# R401H.net
KiCad netlist of a schematic drawn in EAGLE
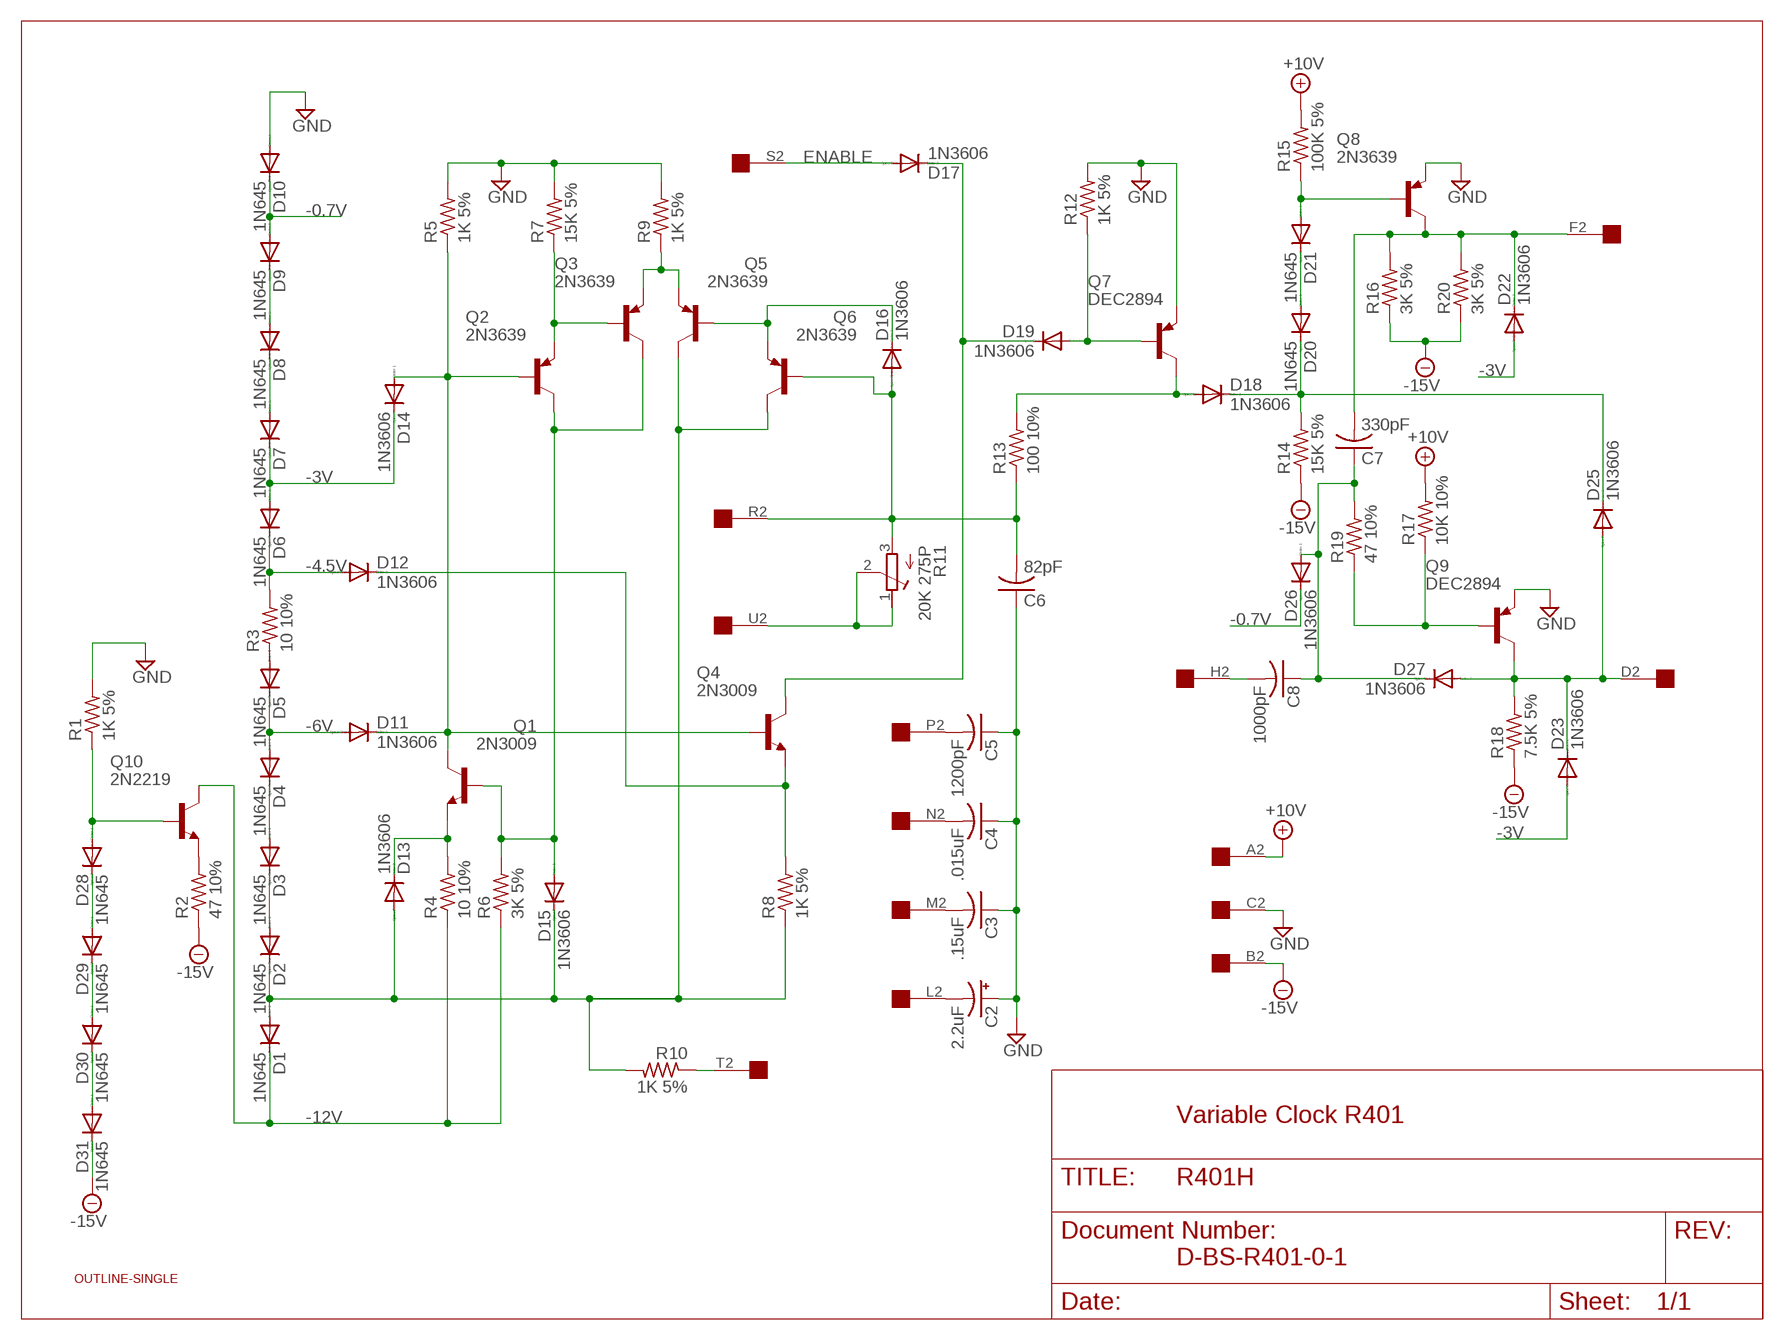
[diagram p0: schematic, sheet 1]

(export (version "E")
  (design (tool "Eeschema 10.0.6"))
  (components
    (comp (ref "C2")
      (value "2.2uF")
      (footprint "eagle-import:E12-4")
      (libsource (lib "eagle-import") (part "CPOL-USE12-4AXIAL"))
    )
    (comp (ref "C3")
      (value ".15uF")
      (footprint "eagle-import:C225-062X268")
      (libsource (lib "eagle-import") (part "C-US225-062X268"))
    )
    (comp (ref "C4")
      (value ".015uF")
      (footprint "eagle-import:C102-043X133")
      (libsource (lib "eagle-import") (part "C-US102-043X133"))
    )
    (comp (ref "C5")
      (value "1200pF")
      (footprint "eagle-import:C150-054X183")
      (libsource (lib "eagle-import") (part "C-US150-054X183"))
    )
    (comp (ref "C6")
      (value "82pF")
      (footprint "eagle-import:C102-043X133")
      (libsource (lib "eagle-import") (part "C-US102-043X133"))
    )
    (comp (ref "C7")
      (value "330pF")
      (footprint "eagle-import:C150-054X183")
      (libsource (lib "eagle-import") (part "C-US150-054X183"))
    )
    (comp (ref "C8")
      (value "1000pF")
      (footprint "eagle-import:C150-054X183")
      (libsource (lib "eagle-import") (part "C-US150-054X183"))
    )
    (comp (ref "D1")
      (value "1N645")
      (footprint "eagle-import:DO35-10")
      (libsource (lib "eagle-import") (part "1N4148DO35-10"))
    )
    (comp (ref "D2")
      (value "1N645")
      (footprint "eagle-import:DO35-10")
      (libsource (lib "eagle-import") (part "1N4148DO35-10"))
    )
    (comp (ref "D3")
      (value "1N645")
      (footprint "eagle-import:DO35-10")
      (libsource (lib "eagle-import") (part "1N4148DO35-10"))
    )
    (comp (ref "D4")
      (value "1N645")
      (footprint "eagle-import:DO35-10")
      (libsource (lib "eagle-import") (part "1N4148DO35-10"))
    )
    (comp (ref "D5")
      (value "1N645")
      (footprint "eagle-import:DO35-10")
      (libsource (lib "eagle-import") (part "1N4148DO35-10"))
    )
    (comp (ref "D6")
      (value "1N645")
      (footprint "eagle-import:DO35-10")
      (libsource (lib "eagle-import") (part "1N4148DO35-10"))
    )
    (comp (ref "D7")
      (value "1N645")
      (footprint "eagle-import:DO35-10")
      (libsource (lib "eagle-import") (part "1N4148DO35-10"))
    )
    (comp (ref "D8")
      (value "1N645")
      (footprint "eagle-import:DO35-10")
      (libsource (lib "eagle-import") (part "1N4148DO35-10"))
    )
    (comp (ref "D9")
      (value "1N645")
      (footprint "eagle-import:DO35-10")
      (libsource (lib "eagle-import") (part "1N4148DO35-10"))
    )
    (comp (ref "D10")
      (value "1N645")
      (footprint "eagle-import:DO35-10")
      (libsource (lib "eagle-import") (part "1N4148DO35-10"))
    )
    (comp (ref "D11")
      (value "1N3606")
      (footprint "eagle-import:DO35-10")
      (libsource (lib "eagle-import") (part "1N4148DO35-10"))
    )
    (comp (ref "D12")
      (value "1N3606")
      (footprint "eagle-import:DO35-10")
      (libsource (lib "eagle-import") (part "1N4148DO35-10"))
    )
    (comp (ref "D13")
      (value "1N3606")
      (footprint "eagle-import:DO35-10")
      (libsource (lib "eagle-import") (part "1N4148DO35-10"))
    )
    (comp (ref "D14")
      (value "1N3606")
      (footprint "eagle-import:DO35-10")
      (libsource (lib "eagle-import") (part "1N4148DO35-10"))
    )
    (comp (ref "D15")
      (value "1N3606")
      (footprint "eagle-import:DO35-10")
      (libsource (lib "eagle-import") (part "1N4148DO35-10"))
    )
    (comp (ref "D16")
      (value "1N3606")
      (footprint "eagle-import:DO35-10")
      (libsource (lib "eagle-import") (part "1N4148DO35-10"))
    )
    (comp (ref "D17")
      (value "1N3606")
      (footprint "eagle-import:DO35-10")
      (libsource (lib "eagle-import") (part "1N4148DO35-10"))
    )
    (comp (ref "D18")
      (value "1N3606")
      (footprint "eagle-import:DO35-10")
      (libsource (lib "eagle-import") (part "1N4148DO35-10"))
    )
    (comp (ref "D19")
      (value "1N3606")
      (footprint "eagle-import:DO35-10")
      (libsource (lib "eagle-import") (part "1N4148DO35-10"))
    )
    (comp (ref "D20")
      (value "1N645")
      (footprint "eagle-import:DO35-10")
      (libsource (lib "eagle-import") (part "1N4148DO35-10"))
    )
    (comp (ref "D21")
      (value "1N645")
      (footprint "eagle-import:DO35-10")
      (libsource (lib "eagle-import") (part "1N4148DO35-10"))
    )
    (comp (ref "D22")
      (value "1N3606")
      (footprint "eagle-import:DO35-10")
      (libsource (lib "eagle-import") (part "1N4148DO35-10"))
    )
    (comp (ref "D23")
      (value "1N3606")
      (footprint "eagle-import:DO35-10")
      (libsource (lib "eagle-import") (part "1N4148DO35-10"))
    )
    (comp (ref "D25")
      (value "1N3606")
      (footprint "eagle-import:DO35-10")
      (libsource (lib "eagle-import") (part "1N4148DO35-10"))
    )
    (comp (ref "D26")
      (value "1N3606")
      (footprint "eagle-import:DO35-10")
      (libsource (lib "eagle-import") (part "1N4148DO35-10"))
    )
    (comp (ref "D27")
      (value "1N3606")
      (footprint "eagle-import:DO35-10")
      (libsource (lib "eagle-import") (part "1N4148DO35-10"))
    )
    (comp (ref "D28")
      (value "1N645")
      (footprint "eagle-import:DO35-10")
      (libsource (lib "eagle-import") (part "1N4148DO35-10"))
    )
    (comp (ref "D29")
      (value "1N645")
      (footprint "eagle-import:DO35-10")
      (libsource (lib "eagle-import") (part "1N4148DO35-10"))
    )
    (comp (ref "D30")
      (value "1N645")
      (footprint "eagle-import:DO35-10")
      (libsource (lib "eagle-import") (part "1N4148DO35-10"))
    )
    (comp (ref "D31")
      (value "1N645")
      (footprint "eagle-import:DO35-10")
      (libsource (lib "eagle-import") (part "1N4148DO35-10"))
    )
    (comp (ref "Q1")
      (value "2N3009")
      (footprint "eagle-import:TO5")
      (libsource (lib "eagle-import") (part "2N2102"))
    )
    (comp (ref "Q2")
      (value "2N3639")
      (footprint "eagle-import:TO39")
      (libsource (lib "eagle-import") (part "2N2904"))
    )
    (comp (ref "Q3")
      (value "2N3639")
      (footprint "eagle-import:TO39")
      (libsource (lib "eagle-import") (part "2N2904"))
    )
    (comp (ref "Q4")
      (value "2N3009")
      (footprint "eagle-import:TO5")
      (libsource (lib "eagle-import") (part "2N2102"))
    )
    (comp (ref "Q5")
      (value "2N3639")
      (footprint "eagle-import:TO39")
      (libsource (lib "eagle-import") (part "2N2904"))
    )
    (comp (ref "Q6")
      (value "2N3639")
      (footprint "eagle-import:TO39")
      (libsource (lib "eagle-import") (part "2N2904"))
    )
    (comp (ref "Q7")
      (value "DEC2894")
      (footprint "eagle-import:TO39")
      (libsource (lib "eagle-import") (part "2N2904"))
    )
    (comp (ref "Q8")
      (value "2N3639")
      (footprint "eagle-import:TO39")
      (libsource (lib "eagle-import") (part "2N2904"))
    )
    (comp (ref "Q9")
      (value "DEC2894")
      (footprint "eagle-import:TO39")
      (libsource (lib "eagle-import") (part "2N2904"))
    )
    (comp (ref "Q10")
      (value "2N2219")
      (footprint "eagle-import:TO5")
      (libsource (lib "eagle-import") (part "2N2102"))
    )
    (comp (ref "R1")
      (value "1K 5%")
      (footprint "eagle-import:0207_10")
      (libsource (lib "eagle-import") (part "R-US_0207/10"))
    )
    (comp (ref "R2")
      (value "47 10%")
      (footprint "eagle-import:0207_10")
      (libsource (lib "eagle-import") (part "R-US_0207/10"))
    )
    (comp (ref "R3")
      (value "10 10%")
      (footprint "eagle-import:0207_10")
      (libsource (lib "eagle-import") (part "R-US_0207/10"))
    )
    (comp (ref "R4")
      (value "10 10%")
      (footprint "eagle-import:0207_10")
      (libsource (lib "eagle-import") (part "R-US_0207/10"))
    )
    (comp (ref "R5")
      (value "1K 5%")
      (footprint "eagle-import:0207_10")
      (libsource (lib "eagle-import") (part "R-US_0207/10"))
    )
    (comp (ref "R6")
      (value "3K 5%")
      (footprint "eagle-import:0207_10")
      (libsource (lib "eagle-import") (part "R-US_0207/10"))
    )
    (comp (ref "R7")
      (value "15K 5%")
      (footprint "eagle-import:0207_10")
      (libsource (lib "eagle-import") (part "R-US_0207/10"))
    )
    (comp (ref "R8")
      (value "1K 5%")
      (footprint "eagle-import:0207_10")
      (libsource (lib "eagle-import") (part "R-US_0207/10"))
    )
    (comp (ref "R9")
      (value "1K 5%")
      (footprint "eagle-import:0207_10")
      (libsource (lib "eagle-import") (part "R-US_0207/10"))
    )
    (comp (ref "R10")
      (value "1K 5%")
      (footprint "eagle-import:0207_10")
      (libsource (lib "eagle-import") (part "R-US_0207/10"))
    )
    (comp (ref "R11")
      (value "20K 275P")
      (footprint "eagle-import:3006Y")
      (libsource (lib "eagle-import") (part "275P"))
    )
    (comp (ref "R12")
      (value "1K 5%")
      (footprint "eagle-import:0207_10")
      (libsource (lib "eagle-import") (part "R-US_0207/10"))
    )
    (comp (ref "R13")
      (value "100 10%")
      (footprint "eagle-import:0207_10")
      (libsource (lib "eagle-import") (part "R-US_0207/10"))
    )
    (comp (ref "R14")
      (value "15K 5%")
      (footprint "eagle-import:0207_10")
      (libsource (lib "eagle-import") (part "R-US_0207/10"))
    )
    (comp (ref "R15")
      (value "100K 5%")
      (footprint "eagle-import:0207_10")
      (libsource (lib "eagle-import") (part "R-US_0207/10"))
    )
    (comp (ref "R16")
      (value "3K 5%")
      (footprint "eagle-import:0207_10")
      (libsource (lib "eagle-import") (part "R-US_0207/10"))
    )
    (comp (ref "R17")
      (value "10K 10%")
      (footprint "eagle-import:0207_10")
      (libsource (lib "eagle-import") (part "R-US_0207/10"))
    )
    (comp (ref "R18")
      (value "7.5K 5%")
      (footprint "eagle-import:0207_10")
      (libsource (lib "eagle-import") (part "R-US_0207/10"))
    )
    (comp (ref "R19")
      (value "47 10%")
      (footprint "eagle-import:0207_10")
      (libsource (lib "eagle-import") (part "R-US_0207/10"))
    )
    (comp (ref "R20")
      (value "3K 5%")
      (footprint "eagle-import:0207_10")
      (libsource (lib "eagle-import") (part "R-US_0207/10"))
    )
    (comp (ref "U$1")
      (value "OUTLINE-SINGLE")
      (footprint "eagle-import:SINGLE")
      (libsource (lib "eagle-import") (part "OUTLINE-SINGLE"))
    )
    (comp (ref "U$2")
      (value "EDGE-1")
      (footprint "eagle-import:EDGE-CON1")
      (libsource (lib "eagle-import") (part "EDGE-1"))
    )
  )
  (nets
    (net (code "1") (name "+10V") (class "Default")
      (node (ref "R15") (pin "2") (pinfunction "2_2") (pintype "passive"))
      (node (ref "R17") (pin "2") (pinfunction "2_2") (pintype "passive"))
      (node (ref "U$2") (pin "A2") (pinfunction "1_A2") (pintype "bidirectional"))
    )
    (net (code "2") (name "-15V") (class "Default")
      (node (ref "D31") (pin "C") (pinfunction "C_C") (pintype "passive"))
      (node (ref "R14") (pin "1") (pinfunction "1_1") (pintype "passive"))
      (node (ref "R16") (pin "1") (pinfunction "1_1") (pintype "passive"))
      (node (ref "R18") (pin "1") (pinfunction "1_1") (pintype "passive"))
      (node (ref "R2") (pin "1") (pinfunction "1_1") (pintype "passive"))
      (node (ref "R20") (pin "1") (pinfunction "1_1") (pintype "passive"))
      (node (ref "U$2") (pin "B2") (pinfunction "1_B2") (pintype "bidirectional"))
    )
    (net (code "3") (name "/-0.7V") (class "Default")
      (node (ref "D10") (pin "C") (pinfunction "C_C") (pintype "passive"))
      (node (ref "D26") (pin "C") (pinfunction "C_C") (pintype "passive"))
      (node (ref "D9") (pin "A") (pinfunction "A_A") (pintype "passive"))
    )
    (net (code "4") (name "/-3V") (class "Default")
      (node (ref "D14") (pin "C") (pinfunction "C_C") (pintype "passive"))
      (node (ref "D22") (pin "A") (pinfunction "A_A") (pintype "passive"))
      (node (ref "D23") (pin "A") (pinfunction "A_A") (pintype "passive"))
      (node (ref "D6") (pin "A") (pinfunction "A_A") (pintype "passive"))
      (node (ref "D7") (pin "C") (pinfunction "C_C") (pintype "passive"))
    )
    (net (code "5") (name "/-4.5V") (class "Default")
      (node (ref "D12") (pin "A") (pinfunction "A_A") (pintype "passive"))
      (node (ref "D6") (pin "C") (pinfunction "C_C") (pintype "passive"))
      (node (ref "R3") (pin "2") (pinfunction "2_2") (pintype "passive"))
    )
    (net (code "6") (name "/-6V") (class "Default")
      (node (ref "D11") (pin "A") (pinfunction "A_A") (pintype "passive"))
      (node (ref "D4") (pin "A") (pinfunction "A_A") (pintype "passive"))
      (node (ref "D5") (pin "C") (pinfunction "C_C") (pintype "passive"))
    )
    (net (code "7") (name "/-12V") (class "Default")
      (node (ref "D1") (pin "C") (pinfunction "C_C") (pintype "passive"))
      (node (ref "Q10") (pin "3") (pinfunction "C_3") (pintype "passive"))
      (node (ref "R4") (pin "1") (pinfunction "1_1") (pintype "passive"))
      (node (ref "R6") (pin "1") (pinfunction "1_1") (pintype "passive"))
    )
    (net (code "8") (name "/ENABLE") (class "Default")
      (node (ref "D17") (pin "A") (pinfunction "A_A") (pintype "passive"))
      (node (ref "U$2") (pin "S2") (pinfunction "1_S2") (pintype "bidirectional"))
    )
    (net (code "9") (name "GND") (class "Default")
      (node (ref "C2") (pin "+") (pinfunction "+_+") (pintype "passive"))
      (node (ref "C3") (pin "1") (pinfunction "1_1") (pintype "passive"))
      (node (ref "C4") (pin "1") (pinfunction "1_1") (pintype "passive"))
      (node (ref "C5") (pin "1") (pinfunction "1_1") (pintype "passive"))
      (node (ref "C6") (pin "1") (pinfunction "1_1") (pintype "passive"))
      (node (ref "D10") (pin "A") (pinfunction "A_A") (pintype "passive"))
      (node (ref "Q7") (pin "1") (pinfunction "E_1") (pintype "passive"))
      (node (ref "Q8") (pin "1") (pinfunction "E_1") (pintype "passive"))
      (node (ref "Q9") (pin "1") (pinfunction "E_1") (pintype "passive"))
      (node (ref "R1") (pin "2") (pinfunction "2_2") (pintype "passive"))
      (node (ref "R12") (pin "2") (pinfunction "2_2") (pintype "passive"))
      (node (ref "R5") (pin "2") (pinfunction "2_2") (pintype "passive"))
      (node (ref "R7") (pin "2") (pinfunction "2_2") (pintype "passive"))
      (node (ref "R9") (pin "2") (pinfunction "2_2") (pintype "passive"))
      (node (ref "U$2") (pin "C2") (pinfunction "1_C2") (pintype "bidirectional"))
    )
    (net (code "10") (name "Net-(C7-Pad1)") (class "Default")
      (node (ref "C7") (pin "1") (pinfunction "1_1") (pintype "passive"))
      (node (ref "C8") (pin "1") (pinfunction "1_1") (pintype "passive"))
      (node (ref "D26") (pin "A") (pinfunction "A_A") (pintype "passive"))
      (node (ref "D27") (pin "C") (pinfunction "C_C") (pintype "passive"))
      (node (ref "R19") (pin "2") (pinfunction "2_2") (pintype "passive"))
    )
    (net (code "11") (name "Net-(D2-PadA)") (class "Default")
      (node (ref "D2") (pin "A") (pinfunction "A_A") (pintype "passive"))
      (node (ref "D3") (pin "C") (pinfunction "C_C") (pintype "passive"))
    )
    (net (code "12") (name "Net-(D3-PadA)") (class "Default")
      (node (ref "D3") (pin "A") (pinfunction "A_A") (pintype "passive"))
      (node (ref "D4") (pin "C") (pinfunction "C_C") (pintype "passive"))
    )
    (net (code "13") (name "Net-(D5-PadA)") (class "Default")
      (node (ref "D5") (pin "A") (pinfunction "A_A") (pintype "passive"))
      (node (ref "R3") (pin "1") (pinfunction "1_1") (pintype "passive"))
    )
    (net (code "14") (name "Net-(D7-PadA)") (class "Default")
      (node (ref "D7") (pin "A") (pinfunction "A_A") (pintype "passive"))
      (node (ref "D8") (pin "C") (pinfunction "C_C") (pintype "passive"))
    )
    (net (code "15") (name "Net-(D8-PadA)") (class "Default")
      (node (ref "D8") (pin "A") (pinfunction "A_A") (pintype "passive"))
      (node (ref "D9") (pin "C") (pinfunction "C_C") (pintype "passive"))
    )
    (net (code "16") (name "Net-(D18-PadC)") (class "Default")
      (node (ref "D18") (pin "C") (pinfunction "C_C") (pintype "passive"))
      (node (ref "D20") (pin "C") (pinfunction "C_C") (pintype "passive"))
      (node (ref "D25") (pin "C") (pinfunction "C_C") (pintype "passive"))
      (node (ref "R14") (pin "2") (pinfunction "2_2") (pintype "passive"))
    )
    (net (code "17") (name "Net-(D20-PadA)") (class "Default")
      (node (ref "D20") (pin "A") (pinfunction "A_A") (pintype "passive"))
      (node (ref "D21") (pin "C") (pinfunction "C_C") (pintype "passive"))
    )
    (net (code "18") (name "Net-(D28-PadC)") (class "Default")
      (node (ref "D28") (pin "C") (pinfunction "C_C") (pintype "passive"))
      (node (ref "D29") (pin "A") (pinfunction "A_A") (pintype "passive"))
    )
    (net (code "19") (name "Net-(D29-PadC)") (class "Default")
      (node (ref "D29") (pin "C") (pinfunction "C_C") (pintype "passive"))
      (node (ref "D30") (pin "A") (pinfunction "A_A") (pintype "passive"))
    )
    (net (code "20") (name "Net-(D30-PadC)") (class "Default")
      (node (ref "D30") (pin "C") (pinfunction "C_C") (pintype "passive"))
      (node (ref "D31") (pin "A") (pinfunction "A_A") (pintype "passive"))
    )
    (net (code "21") (name "Net-(Q1-B)") (class "Default")
      (node (ref "D15") (pin "A") (pinfunction "A_A") (pintype "passive"))
      (node (ref "Q1") (pin "2") (pinfunction "B_2") (pintype "passive"))
      (node (ref "Q2") (pin "3") (pinfunction "C_3") (pintype "passive"))
      (node (ref "Q3") (pin "3") (pinfunction "C_3") (pintype "passive"))
      (node (ref "R6") (pin "2") (pinfunction "2_2") (pintype "passive"))
    )
    (net (code "22") (name "Net-(Q1-C)") (class "Default")
      (node (ref "D11") (pin "C") (pinfunction "C_C") (pintype "passive"))
      (node (ref "D14") (pin "A") (pinfunction "A_A") (pintype "passive"))
      (node (ref "Q1") (pin "3") (pinfunction "C_3") (pintype "passive"))
      (node (ref "Q2") (pin "2") (pinfunction "B_2") (pintype "passive"))
      (node (ref "Q4") (pin "2") (pinfunction "B_2") (pintype "passive"))
      (node (ref "R5") (pin "1") (pinfunction "1_1") (pintype "passive"))
    )
    (net (code "23") (name "Net-(Q1-E)") (class "Default")
      (node (ref "D13") (pin "C") (pinfunction "C_C") (pintype "passive"))
      (node (ref "Q1") (pin "1") (pinfunction "E_1") (pintype "passive"))
      (node (ref "R4") (pin "2") (pinfunction "2_2") (pintype "passive"))
    )
    (net (code "24") (name "Net-(Q2-E)") (class "Default")
      (node (ref "Q2") (pin "1") (pinfunction "E_1") (pintype "passive"))
      (node (ref "Q3") (pin "2") (pinfunction "B_2") (pintype "passive"))
      (node (ref "R7") (pin "1") (pinfunction "1_1") (pintype "passive"))
    )
    (net (code "25") (name "Net-(Q3-E)") (class "Default")
      (node (ref "Q3") (pin "1") (pinfunction "E_1") (pintype "passive"))
      (node (ref "Q5") (pin "1") (pinfunction "E_1") (pintype "passive"))
      (node (ref "R9") (pin "1") (pinfunction "1_1") (pintype "passive"))
    )
    (net (code "26") (name "Net-(Q4-C)") (class "Default")
      (node (ref "D17") (pin "C") (pinfunction "C_C") (pintype "passive"))
      (node (ref "D19") (pin "C") (pinfunction "C_C") (pintype "passive"))
      (node (ref "Q4") (pin "3") (pinfunction "C_3") (pintype "passive"))
    )
    (net (code "27") (name "Net-(Q4-E)") (class "Default")
      (node (ref "D12") (pin "C") (pinfunction "C_C") (pintype "passive"))
      (node (ref "Q4") (pin "1") (pinfunction "E_1") (pintype "passive"))
      (node (ref "R8") (pin "2") (pinfunction "2_2") (pintype "passive"))
    )
    (net (code "28") (name "Net-(Q5-B)") (class "Default")
      (node (ref "D16") (pin "C") (pinfunction "C_C") (pintype "passive"))
      (node (ref "Q5") (pin "2") (pinfunction "B_2") (pintype "passive"))
      (node (ref "Q6") (pin "1") (pinfunction "E_1") (pintype "passive"))
    )
    (net (code "29") (name "Net-(Q5-C)") (class "Default")
      (node (ref "D1") (pin "A") (pinfunction "A_A") (pintype "passive"))
      (node (ref "D13") (pin "A") (pinfunction "A_A") (pintype "passive"))
      (node (ref "D15") (pin "C") (pinfunction "C_C") (pintype "passive"))
      (node (ref "D2") (pin "C") (pinfunction "C_C") (pintype "passive"))
      (node (ref "Q5") (pin "3") (pinfunction "C_3") (pintype "passive"))
      (node (ref "Q6") (pin "3") (pinfunction "C_3") (pintype "passive"))
      (node (ref "R10") (pin "2") (pinfunction "2_2") (pintype "passive"))
      (node (ref "R8") (pin "1") (pinfunction "1_1") (pintype "passive"))
    )
    (net (code "30") (name "Net-(Q6-B)") (class "Default")
      (node (ref "C6") (pin "2") (pinfunction "2_2") (pintype "passive"))
      (node (ref "D16") (pin "A") (pinfunction "A_A") (pintype "passive"))
      (node (ref "Q6") (pin "2") (pinfunction "B_2") (pintype "passive"))
      (node (ref "R11") (pin "3") (pinfunction "E_3") (pintype "passive"))
      (node (ref "R13") (pin "1") (pinfunction "1_1") (pintype "passive"))
      (node (ref "U$2") (pin "R2") (pinfunction "1_R2") (pintype "bidirectional"))
    )
    (net (code "31") (name "Net-(Q7-B)") (class "Default")
      (node (ref "D19") (pin "A") (pinfunction "A_A") (pintype "passive"))
      (node (ref "Q7") (pin "2") (pinfunction "B_2") (pintype "passive"))
      (node (ref "R12") (pin "1") (pinfunction "1_1") (pintype "passive"))
    )
    (net (code "32") (name "Net-(Q7-C)") (class "Default")
      (node (ref "D18") (pin "A") (pinfunction "A_A") (pintype "passive"))
      (node (ref "Q7") (pin "3") (pinfunction "C_3") (pintype "passive"))
      (node (ref "R13") (pin "2") (pinfunction "2_2") (pintype "passive"))
    )
    (net (code "33") (name "Net-(Q8-B)") (class "Default")
      (node (ref "D21") (pin "A") (pinfunction "A_A") (pintype "passive"))
      (node (ref "Q8") (pin "2") (pinfunction "B_2") (pintype "passive"))
      (node (ref "R15") (pin "1") (pinfunction "1_1") (pintype "passive"))
    )
    (net (code "34") (name "Net-(Q8-C)") (class "Default")
      (node (ref "C7") (pin "2") (pinfunction "2_2") (pintype "passive"))
      (node (ref "D22") (pin "C") (pinfunction "C_C") (pintype "passive"))
      (node (ref "Q8") (pin "3") (pinfunction "C_3") (pintype "passive"))
      (node (ref "R16") (pin "2") (pinfunction "2_2") (pintype "passive"))
      (node (ref "R20") (pin "2") (pinfunction "2_2") (pintype "passive"))
      (node (ref "U$2") (pin "F2") (pinfunction "1_F2") (pintype "bidirectional"))
    )
    (net (code "35") (name "Net-(Q9-B)") (class "Default")
      (node (ref "Q9") (pin "2") (pinfunction "B_2") (pintype "passive"))
      (node (ref "R17") (pin "1") (pinfunction "1_1") (pintype "passive"))
      (node (ref "R19") (pin "1") (pinfunction "1_1") (pintype "passive"))
    )
    (net (code "36") (name "Net-(Q9-C)") (class "Default")
      (node (ref "D23") (pin "C") (pinfunction "C_C") (pintype "passive"))
      (node (ref "D25") (pin "A") (pinfunction "A_A") (pintype "passive"))
      (node (ref "D27") (pin "A") (pinfunction "A_A") (pintype "passive"))
      (node (ref "Q9") (pin "3") (pinfunction "C_3") (pintype "passive"))
      (node (ref "R18") (pin "2") (pinfunction "2_2") (pintype "passive"))
      (node (ref "U$2") (pin "D2") (pinfunction "1_D2") (pintype "bidirectional"))
    )
    (net (code "37") (name "Net-(Q10-B)") (class "Default")
      (node (ref "D28") (pin "A") (pinfunction "A_A") (pintype "passive"))
      (node (ref "Q10") (pin "2") (pinfunction "B_2") (pintype "passive"))
      (node (ref "R1") (pin "1") (pinfunction "1_1") (pintype "passive"))
    )
    (net (code "38") (name "Net-(Q10-E)") (class "Default")
      (node (ref "Q10") (pin "1") (pinfunction "E_1") (pintype "passive"))
      (node (ref "R2") (pin "2") (pinfunction "2_2") (pintype "passive"))
    )
    (net (code "39") (name "Net-(R11-A)") (class "Default")
      (node (ref "R11") (pin "1") (pinfunction "A_1") (pintype "passive"))
      (node (ref "R11") (pin "2") (pinfunction "S_2") (pintype "passive"))
      (node (ref "U$2") (pin "U2") (pinfunction "1_U2") (pintype "bidirectional"))
    )
    (net (code "40") (name "Net-(U$2G-1)") (class "Default")
      (node (ref "C8") (pin "2") (pinfunction "2_2") (pintype "passive"))
      (node (ref "U$2") (pin "H2") (pinfunction "1_H2") (pintype "bidirectional"))
    )
    (net (code "41") (name "Net-(U$2J-1)") (class "Default")
      (node (ref "C2") (pin "-") (pinfunction "-_-") (pintype "passive"))
      (node (ref "U$2") (pin "L2") (pinfunction "1_L2") (pintype "bidirectional"))
    )
    (net (code "42") (name "Net-(U$2K-1)") (class "Default")
      (node (ref "C3") (pin "2") (pinfunction "2_2") (pintype "passive"))
      (node (ref "U$2") (pin "M2") (pinfunction "1_M2") (pintype "bidirectional"))
    )
    (net (code "43") (name "Net-(U$2L-1)") (class "Default")
      (node (ref "C4") (pin "2") (pinfunction "2_2") (pintype "passive"))
      (node (ref "U$2") (pin "N2") (pinfunction "1_N2") (pintype "bidirectional"))
    )
    (net (code "44") (name "Net-(U$2M-1)") (class "Default")
      (node (ref "C5") (pin "2") (pinfunction "2_2") (pintype "passive"))
      (node (ref "U$2") (pin "P2") (pinfunction "1_P2") (pintype "bidirectional"))
    )
    (net (code "45") (name "Net-(U$2P-1)") (class "Default")
      (node (ref "R10") (pin "1") (pinfunction "1_1") (pintype "passive"))
      (node (ref "U$2") (pin "T2") (pinfunction "1_T2") (pintype "bidirectional"))
    )
  )
)
